# EMMC_SD.net
KiCad netlist of a schematic drawn in Altium Designer
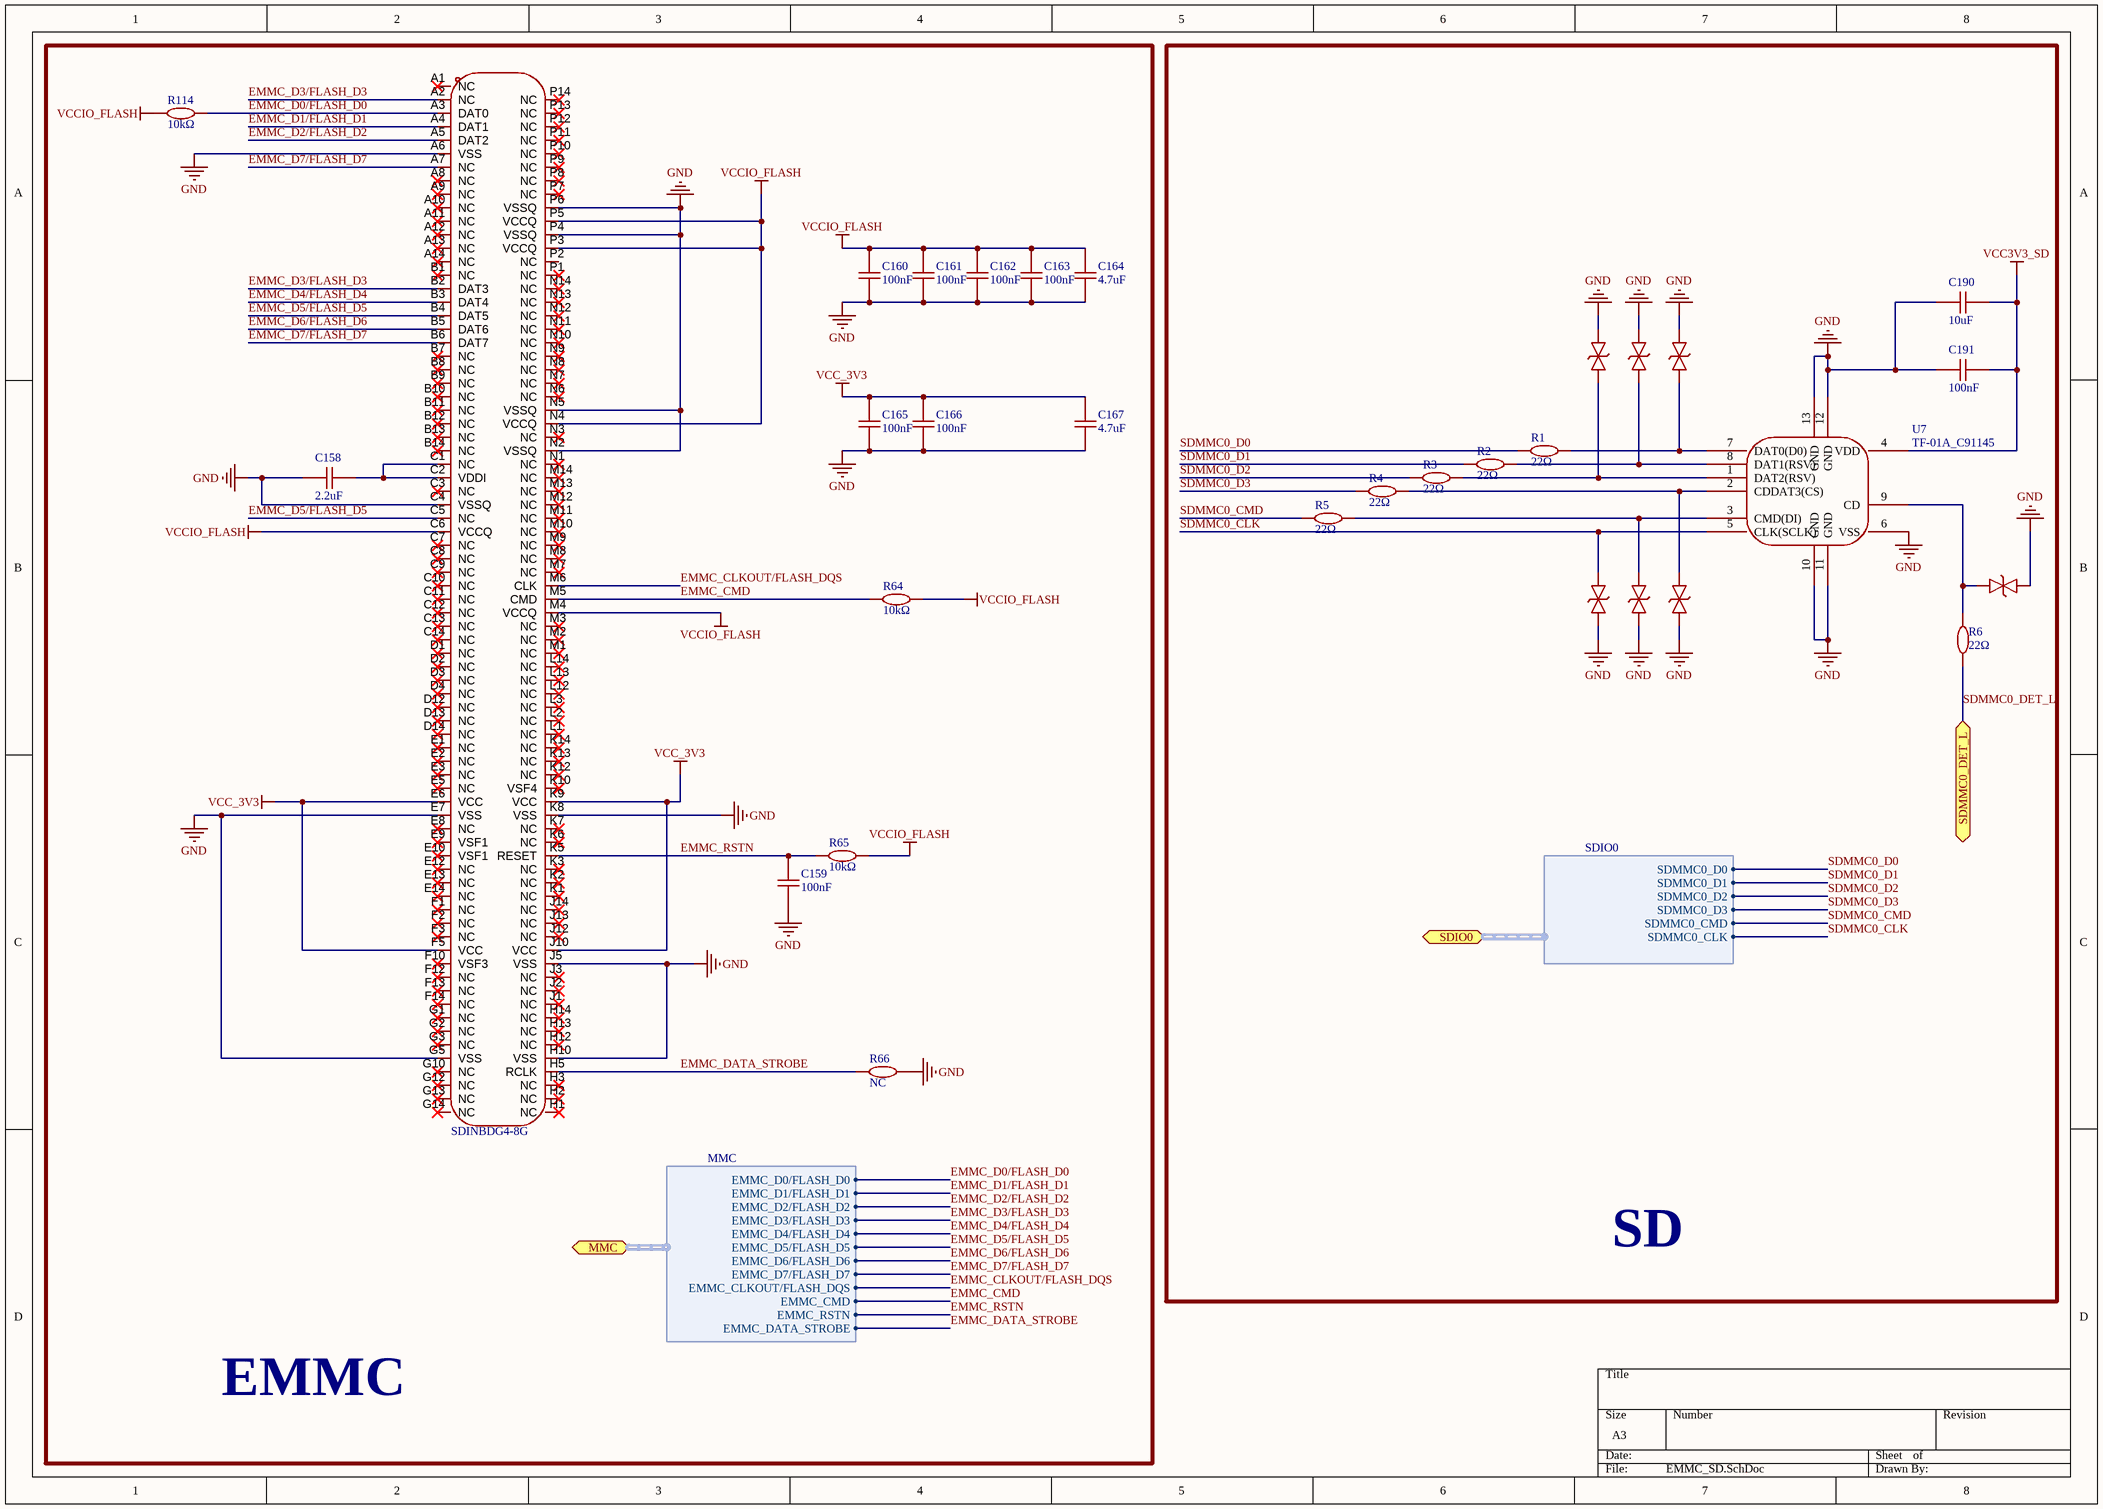
[diagram p0: EMMC_SD.SchDoc]

(export (version "E")
  (design (tool "Eeschema 10.0.6"))
  (components
    (comp (ref "C158")
      (value "2.2uF")
      (footprint "C0402")
      (description "50V 2.2uF NP0 0402 Ceramic Capacitors ROHS")
      (libsource (lib "RLC") (part "2.2uF"))
    )
    (comp (ref "C159")
      (value "100nF")
      (footprint "C0402")
      (description "50V 100nF X7R ±10% 0402 Ceramic Capacitors ROHS")
      (libsource (lib "RLC") (part "100nF"))
    )
    (comp (ref "C160")
      (value "100nF")
      (footprint "C0402")
      (description "50V 100nF X7R ±10% 0402 Ceramic Capacitors ROHS")
      (libsource (lib "RLC") (part "100nF"))
    )
    (comp (ref "C161")
      (value "100nF")
      (footprint "C0402")
      (description "50V 100nF X7R ±10% 0402 Ceramic Capacitors ROHS")
      (libsource (lib "RLC") (part "100nF"))
    )
    (comp (ref "C162")
      (value "100nF")
      (footprint "C0402")
      (description "50V 100nF X7R ±10% 0402 Ceramic Capacitors ROHS")
      (libsource (lib "RLC") (part "100nF"))
    )
    (comp (ref "C163")
      (value "100nF")
      (footprint "C0402")
      (description "50V 100nF X7R ±10% 0402 Ceramic Capacitors ROHS")
      (libsource (lib "RLC") (part "100nF"))
    )
    (comp (ref "C164")
      (value "4.7uF")
      (footprint "C0402")
      (description "10V 4.7uF X5R ±20% 0402 Ceramic Capacitors ROHS")
      (libsource (lib "RLC") (part "4.7uF"))
    )
    (comp (ref "C165")
      (value "100nF")
      (footprint "C0402")
      (description "50V 100nF X7R ±10% 0402 Ceramic Capacitors ROHS")
      (libsource (lib "RLC") (part "100nF"))
    )
    (comp (ref "C166")
      (value "100nF")
      (footprint "C0402")
      (description "50V 100nF X7R ±10% 0402 Ceramic Capacitors ROHS")
      (libsource (lib "RLC") (part "100nF"))
    )
    (comp (ref "C167")
      (value "4.7uF")
      (footprint "C0402")
      (description "10V 4.7uF X5R ±20% 0402 Ceramic Capacitors ROHS")
      (libsource (lib "RLC") (part "4.7uF"))
    )
    (comp (ref "C190")
      (value "10uF")
      (footprint "C0603")
      (description "10V 10uF X5R ±10% 0603 Ceramic Capacitors ROHS")
      (libsource (lib "RLC") (part "10uF"))
    )
    (comp (ref "C191")
      (value "100nF")
      (footprint "C0402")
      (description "50V 100nF X7R ±10% 0402 Ceramic Capacitors ROHS")
      (libsource (lib "RLC") (part "100nF"))
    )
    (comp (ref "R1")
      (value "22Ω")
      (footprint "R0402")
      (description "62.5mW 33Ω 50V ±100ppm/℃ Thick Film Resistor ±1% 0402 Chip Resistor - Surface Mount ROHS")
      (libsource (lib "RLC") (part "22Ω"))
    )
    (comp (ref "R2")
      (value "22Ω")
      (footprint "R0402")
      (description "62.5mW 33Ω 50V ±100ppm/℃ Thick Film Resistor ±1% 0402 Chip Resistor - Surface Mount ROHS")
      (libsource (lib "RLC") (part "22Ω"))
    )
    (comp (ref "R3")
      (value "22Ω")
      (footprint "R0402")
      (description "62.5mW 33Ω 50V ±100ppm/℃ Thick Film Resistor ±1% 0402 Chip Resistor - Surface Mount ROHS")
      (libsource (lib "RLC") (part "22Ω"))
    )
    (comp (ref "R4")
      (value "22Ω")
      (footprint "R0402")
      (description "62.5mW 33Ω 50V ±100ppm/℃ Thick Film Resistor ±1% 0402 Chip Resistor - Surface Mount ROHS")
      (libsource (lib "RLC") (part "22Ω"))
    )
    (comp (ref "R5")
      (value "22Ω")
      (footprint "R0402")
      (description "62.5mW 33Ω 50V ±100ppm/℃ Thick Film Resistor ±1% 0402 Chip Resistor - Surface Mount ROHS")
      (libsource (lib "RLC") (part "22Ω"))
    )
    (comp (ref "R6")
      (value "22Ω")
      (footprint "R0402")
      (description "62.5mW 33Ω 50V ±100ppm/℃ Thick Film Resistor ±1% 0402 Chip Resistor - Surface Mount ROHS")
      (libsource (lib "RLC") (part "22Ω"))
    )
    (comp (ref "R64")
      (value "10kΩ")
      (footprint "R0402")
      (description "62.5mW 10kΩ 50V ±100ppm/℃ Thick Film Resistor ±1% 0402 Chip Resistor - Surface Mount ROHS")
      (libsource (lib "RLC") (part "10kΩ"))
    )
    (comp (ref "R65")
      (value "10kΩ")
      (footprint "R0402")
      (description "62.5mW 10kΩ 50V ±100ppm/℃ Thick Film Resistor ±1% 0402 Chip Resistor - Surface Mount ROHS")
      (libsource (lib "RLC") (part "10kΩ"))
    )
    (comp (ref "R66")
      (value "NC")
      (footprint "R0402")
      (description "62.5mW 10kΩ 50V ±100ppm/℃ Thick Film Resistor ±1% 0402 Chip Resistor - Surface Mount ROHS")
      (libsource (lib "RLC") (part "10kΩ"))
    )
    (comp (ref "R114")
      (value "10kΩ")
      (footprint "R0402")
      (description "62.5mW 10kΩ 50V ±100ppm/℃ Thick Film Resistor ±1% 0402 Chip Resistor - Surface Mount ROHS")
      (libsource (lib "RLC") (part "10kΩ"))
    )
    (comp (ref "U3")
      (value "SDINBDG4-8G")
      (footprint "FBGA-153_L13.0-W11.5-P0.50_KLMAG1JETD-B041")
      (libsource (lib "IC") (part "SDINBDG4-8G"))
    )
    (comp (ref "U4")
      (value "ESD5451N")
      (footprint "DFN1006-2L-BI")
      (description "9A 9.8V 8V Bidirectional 5V DFN1006-2L TVS Diodes ROHS")
      (fields (field (name "MANUFACTURER") "HXY MOSFET(华轩阳电子)"))
      (libsource (lib "LED") (part "ESD5451N_C5261080"))
    )
    (comp (ref "U5")
      (value "ESD5451N")
      (footprint "DFN1006-2L-BI")
      (description "9A 9.8V 8V Bidirectional 5V DFN1006-2L TVS Diodes ROHS")
      (fields (field (name "MANUFACTURER") "HXY MOSFET(华轩阳电子)"))
      (libsource (lib "LED") (part "ESD5451N_C5261080"))
    )
    (comp (ref "U6")
      (value "ESD5451N")
      (footprint "DFN1006-2L-BI")
      (description "9A 9.8V 8V Bidirectional 5V DFN1006-2L TVS Diodes ROHS")
      (fields (field (name "MANUFACTURER") "HXY MOSFET(华轩阳电子)"))
      (libsource (lib "LED") (part "ESD5451N_C5261080"))
    )
    (comp (ref "U7")
      (value "TF-01A_C91145")
      (footprint "TF-SMD_TF-01A")
      (description "Push-Push 1.85mm Connector and Ejector MicroSD Card (TF Card) SMD PC Card Sockets ROHS")
      (libsource (lib "IC") (part "TF-01A_C91145"))
    )
    (comp (ref "U8")
      (value "ESD5451N")
      (footprint "DFN1006-2L-BI")
      (description "9A 9.8V 8V Bidirectional 5V DFN1006-2L TVS Diodes ROHS")
      (fields (field (name "MANUFACTURER") "HXY MOSFET(华轩阳电子)"))
      (libsource (lib "LED") (part "ESD5451N_C5261080"))
    )
    (comp (ref "U9")
      (value "ESD5451N")
      (footprint "DFN1006-2L-BI")
      (description "9A 9.8V 8V Bidirectional 5V DFN1006-2L TVS Diodes ROHS")
      (fields (field (name "MANUFACTURER") "HXY MOSFET(华轩阳电子)"))
      (libsource (lib "LED") (part "ESD5451N_C5261080"))
    )
    (comp (ref "U10")
      (value "ESD5451N")
      (footprint "DFN1006-2L-BI")
      (description "9A 9.8V 8V Bidirectional 5V DFN1006-2L TVS Diodes ROHS")
      (fields (field (name "MANUFACTURER") "HXY MOSFET(华轩阳电子)"))
      (libsource (lib "LED") (part "ESD5451N_C5261080"))
    )
    (comp (ref "U11")
      (value "ESD5451N")
      (footprint "DFN1006-2L-BI")
      (description "9A 9.8V 8V Bidirectional 5V DFN1006-2L TVS Diodes ROHS")
      (fields (field (name "MANUFACTURER") "HXY MOSFET(华轩阳电子)"))
      (libsource (lib "LED") (part "ESD5451N_C5261080"))
    )
  )
  (nets
    (net (code "3") (name "/EMMC_CLKOUT{slash}FLASH_DQS") (class "Default")
      (node (ref "U3") (pin "M6") (pinfunction "CLK_M6") (pintype "passive"))
    )
    (net (code "4") (name "/EMMC_CMD") (class "Default")
      (node (ref "R64") (pin "1") (pinfunction "1_1") (pintype "passive"))
      (node (ref "U3") (pin "M5") (pinfunction "CMD_M5") (pintype "passive"))
    )
    (net (code "5") (name "/EMMC_D0{slash}FLASH_D0") (class "Default")
      (node (ref "R114") (pin "2") (pinfunction "2_2") (pintype "passive"))
      (node (ref "U3") (pin "A3") (pinfunction "DAT0_A3") (pintype "passive"))
    )
    (net (code "6") (name "/EMMC_D1{slash}FLASH_D1") (class "Default")
      (node (ref "U3") (pin "A4") (pinfunction "DAT1_A4") (pintype "passive"))
    )
    (net (code "7") (name "/EMMC_D2{slash}FLASH_D2") (class "Default")
      (node (ref "U3") (pin "A5") (pinfunction "DAT2_A5") (pintype "passive"))
    )
    (net (code "8") (name "/EMMC_D3{slash}FLASH_D3") (class "Default")
      (node (ref "U3") (pin "A2") (pinfunction "NC_A2") (pintype "passive"))
      (node (ref "U3") (pin "B2") (pinfunction "DAT3_B2") (pintype "passive"))
    )
    (net (code "9") (name "/EMMC_D4{slash}FLASH_D4") (class "Default")
      (node (ref "U3") (pin "B3") (pinfunction "DAT4_B3") (pintype "passive"))
    )
    (net (code "10") (name "/EMMC_D5{slash}FLASH_D5") (class "Default")
      (node (ref "U3") (pin "B4") (pinfunction "DAT5_B4") (pintype "passive"))
      (node (ref "U3") (pin "C5") (pinfunction "NC_C5") (pintype "passive"))
    )
    (net (code "11") (name "/EMMC_D6{slash}FLASH_D6") (class "Default")
      (node (ref "U3") (pin "B5") (pinfunction "DAT6_B5") (pintype "passive"))
    )
    (net (code "12") (name "/EMMC_D7{slash}FLASH_D7") (class "Default")
      (node (ref "U3") (pin "A7") (pinfunction "NC_A7") (pintype "passive"))
      (node (ref "U3") (pin "B6") (pinfunction "DAT7_B6") (pintype "passive"))
    )
    (net (code "13") (name "/EMMC_DATA_STROBE") (class "Default")
      (node (ref "R66") (pin "1") (pinfunction "1_1") (pintype "passive"))
      (node (ref "U3") (pin "H5") (pinfunction "RCLK_H5") (pintype "passive"))
    )
    (net (code "14") (name "/EMMC_RSTN") (class "Default")
      (node (ref "C159") (pin "2") (pinfunction "2_2") (pintype "passive"))
      (node (ref "R65") (pin "1") (pinfunction "1_1") (pintype "passive"))
      (node (ref "U3") (pin "K5") (pinfunction "RESET_K5") (pintype "passive"))
    )
    (net (code "15") (name "/SDMMC0_CLK") (class "Default")
      (node (ref "U7") (pin "5") (pinfunction "CLK(SCLK)_5") (pintype "passive"))
      (node (ref "U8") (pin "2") (pinfunction "2_2") (pintype "passive"))
    )
    (net (code "16") (name "/SDMMC0_CMD") (class "Default")
      (node (ref "R5") (pin "1") (pinfunction "1_1") (pintype "passive"))
    )
    (net (code "17") (name "/SDMMC0_D0") (class "Default")
      (node (ref "R1") (pin "1") (pinfunction "1_1") (pintype "passive"))
    )
    (net (code "18") (name "/SDMMC0_D1") (class "Default")
      (node (ref "R2") (pin "1") (pinfunction "1_1") (pintype "passive"))
    )
    (net (code "19") (name "/SDMMC0_D2") (class "Default")
      (node (ref "R3") (pin "1") (pinfunction "1_1") (pintype "passive"))
    )
    (net (code "20") (name "/SDMMC0_D3") (class "Default")
      (node (ref "R4") (pin "1") (pinfunction "1_1") (pintype "passive"))
    )
    (net (code "21") (name "/SDMMC0_DET_L") (class "Default")
      (node (ref "R6") (pin "1") (pinfunction "1_1") (pintype "passive"))
    )
    (net (code "24") (name "GND") (class "Default")
      (node (ref "C158") (pin "1") (pinfunction "1_1") (pintype "passive"))
      (node (ref "C159") (pin "1") (pinfunction "1_1") (pintype "passive"))
      (node (ref "C160") (pin "1") (pinfunction "1_1") (pintype "passive"))
      (node (ref "C161") (pin "1") (pinfunction "1_1") (pintype "passive"))
      (node (ref "C162") (pin "1") (pinfunction "1_1") (pintype "passive"))
      (node (ref "C163") (pin "1") (pinfunction "1_1") (pintype "passive"))
      (node (ref "C164") (pin "1") (pinfunction "1_1") (pintype "passive"))
      (node (ref "C165") (pin "1") (pinfunction "1_1") (pintype "passive"))
      (node (ref "C166") (pin "1") (pinfunction "1_1") (pintype "passive"))
      (node (ref "C167") (pin "1") (pinfunction "1_1") (pintype "passive"))
      (node (ref "C190") (pin "1") (pinfunction "1_1") (pintype "passive"))
      (node (ref "C191") (pin "1") (pinfunction "1_1") (pintype "passive"))
      (node (ref "R66") (pin "2") (pinfunction "2_2") (pintype "passive"))
      (node (ref "U10") (pin "1") (pinfunction "1_1") (pintype "passive"))
      (node (ref "U11") (pin "1") (pinfunction "1_1") (pintype "passive"))
      (node (ref "U3") (pin "A6") (pinfunction "VSS_A6") (pintype "passive"))
      (node (ref "U3") (pin "C4") (pinfunction "VSSQ_C4") (pintype "passive"))
      (node (ref "U3") (pin "E7") (pinfunction "VSS_E7") (pintype "passive"))
      (node (ref "U3") (pin "G5") (pinfunction "VSS_G5") (pintype "passive"))
      (node (ref "U3") (pin "H10") (pinfunction "VSS_H10") (pintype "passive"))
      (node (ref "U3") (pin "J5") (pinfunction "VSS_J5") (pintype "passive"))
      (node (ref "U3") (pin "K8") (pinfunction "VSS_K8") (pintype "passive"))
      (node (ref "U3") (pin "N2") (pinfunction "VSSQ_N2") (pintype "passive"))
      (node (ref "U3") (pin "N5") (pinfunction "VSSQ_N5") (pintype "passive"))
      (node (ref "U3") (pin "P4") (pinfunction "VSSQ_P4") (pintype "passive"))
      (node (ref "U3") (pin "P6") (pinfunction "VSSQ_P6") (pintype "passive"))
      (node (ref "U4") (pin "2") (pinfunction "2_2") (pintype "passive"))
      (node (ref "U5") (pin "2") (pinfunction "2_2") (pintype "passive"))
      (node (ref "U6") (pin "2") (pinfunction "2_2") (pintype "passive"))
      (node (ref "U7") (pin "10") (pinfunction "GND_10") (pintype "passive"))
      (node (ref "U7") (pin "11") (pinfunction "GND_11") (pintype "passive"))
      (node (ref "U7") (pin "12") (pinfunction "GND_12") (pintype "passive"))
      (node (ref "U7") (pin "13") (pinfunction "GND_13") (pintype "passive"))
      (node (ref "U7") (pin "6") (pinfunction "VSS_6") (pintype "passive"))
      (node (ref "U8") (pin "1") (pinfunction "1_1") (pintype "passive"))
      (node (ref "U9") (pin "1") (pinfunction "1_1") (pintype "passive"))
    )
    (net (code "25") (name "Net-(U3-VDDI)") (class "Default")
      (node (ref "C158") (pin "2") (pinfunction "2_2") (pintype "passive"))
      (node (ref "U3") (pin "C1") (pinfunction "NC_C1") (pintype "passive"))
      (node (ref "U3") (pin "C2") (pinfunction "VDDI_C2") (pintype "passive"))
    )
    (net (code "26") (name "Net-(U7-CD)") (class "Default")
      (node (ref "R6") (pin "2") (pinfunction "2_2") (pintype "passive"))
      (node (ref "U11") (pin "2") (pinfunction "2_2") (pintype "passive"))
      (node (ref "U7") (pin "9") (pinfunction "CD_9") (pintype "passive"))
    )
    (net (code "27") (name "Net-(U7-CDDAT3(CS))") (class "Default")
      (node (ref "R4") (pin "2") (pinfunction "2_2") (pintype "passive"))
      (node (ref "U10") (pin "2") (pinfunction "2_2") (pintype "passive"))
      (node (ref "U7") (pin "2") (pinfunction "CDDAT3(CS)_2") (pintype "passive"))
    )
    (net (code "28") (name "Net-(U7-CMD(DI))") (class "Default")
      (node (ref "R5") (pin "2") (pinfunction "2_2") (pintype "passive"))
      (node (ref "U7") (pin "3") (pinfunction "CMD(DI)_3") (pintype "passive"))
      (node (ref "U9") (pin "2") (pinfunction "2_2") (pintype "passive"))
    )
    (net (code "29") (name "Net-(U7-DAT0(D0))") (class "Default")
      (node (ref "R1") (pin "2") (pinfunction "2_2") (pintype "passive"))
      (node (ref "U6") (pin "1") (pinfunction "1_1") (pintype "passive"))
      (node (ref "U7") (pin "7") (pinfunction "DAT0(D0)_7") (pintype "passive"))
    )
    (net (code "30") (name "Net-(U7-DAT1(RSV))") (class "Default")
      (node (ref "R2") (pin "2") (pinfunction "2_2") (pintype "passive"))
      (node (ref "U5") (pin "1") (pinfunction "1_1") (pintype "passive"))
      (node (ref "U7") (pin "8") (pinfunction "DAT1(RSV)_8") (pintype "passive"))
    )
    (net (code "31") (name "Net-(U7-DAT2(RSV))") (class "Default")
      (node (ref "R3") (pin "2") (pinfunction "2_2") (pintype "passive"))
      (node (ref "U4") (pin "1") (pinfunction "1_1") (pintype "passive"))
      (node (ref "U7") (pin "1") (pinfunction "DAT2(RSV)_1") (pintype "passive"))
    )
    (net (code "32") (name "VCC3V3_SD") (class "Default")
      (node (ref "C190") (pin "2") (pinfunction "2_2") (pintype "passive"))
      (node (ref "C191") (pin "2") (pinfunction "2_2") (pintype "passive"))
      (node (ref "U7") (pin "4") (pinfunction "VDD_4") (pintype "passive"))
    )
    (net (code "33") (name "VCCIO_FLASH") (class "Default")
      (node (ref "C160") (pin "2") (pinfunction "2_2") (pintype "passive"))
      (node (ref "C161") (pin "2") (pinfunction "2_2") (pintype "passive"))
      (node (ref "C162") (pin "2") (pinfunction "2_2") (pintype "passive"))
      (node (ref "C163") (pin "2") (pinfunction "2_2") (pintype "passive"))
      (node (ref "C164") (pin "2") (pinfunction "2_2") (pintype "passive"))
      (node (ref "R114") (pin "1") (pinfunction "1_1") (pintype "passive"))
      (node (ref "R64") (pin "2") (pinfunction "2_2") (pintype "passive"))
      (node (ref "R65") (pin "2") (pinfunction "2_2") (pintype "passive"))
      (node (ref "U3") (pin "C6") (pinfunction "VCCQ_C6") (pintype "passive"))
      (node (ref "U3") (pin "M4") (pinfunction "VCCQ_M4") (pintype "passive"))
      (node (ref "U3") (pin "N4") (pinfunction "VCCQ_N4") (pintype "passive"))
      (node (ref "U3") (pin "P3") (pinfunction "VCCQ_P3") (pintype "passive"))
      (node (ref "U3") (pin "P5") (pinfunction "VCCQ_P5") (pintype "passive"))
    )
    (net (code "34") (name "VCC_3V3") (class "Default")
      (node (ref "C165") (pin "2") (pinfunction "2_2") (pintype "passive"))
      (node (ref "C166") (pin "2") (pinfunction "2_2") (pintype "passive"))
      (node (ref "C167") (pin "2") (pinfunction "2_2") (pintype "passive"))
      (node (ref "U3") (pin "E6") (pinfunction "VCC_E6") (pintype "passive"))
      (node (ref "U3") (pin "F5") (pinfunction "VCC_F5") (pintype "passive"))
      (node (ref "U3") (pin "J10") (pinfunction "VCC_J10") (pintype "passive"))
      (node (ref "U3") (pin "K9") (pinfunction "VCC_K9") (pintype "passive"))
    )
    (net (code "35") (name "unconnected-(U3-NC-PadA1)") (class "Default")
      (node (ref "U3") (pin "A1") (pinfunction "NC_A1") (pintype "passive+no_connect"))
    )
    (net (code "36") (name "unconnected-(U3-NC-PadA8)") (class "Default")
      (node (ref "U3") (pin "A8") (pinfunction "NC_A8") (pintype "passive+no_connect"))
    )
    (net (code "37") (name "unconnected-(U3-NC-PadA9)") (class "Default")
      (node (ref "U3") (pin "A9") (pinfunction "NC_A9") (pintype "passive+no_connect"))
    )
    (net (code "38") (name "unconnected-(U3-NC-PadA10)") (class "Default")
      (node (ref "U3") (pin "A10") (pinfunction "NC_A10") (pintype "passive+no_connect"))
    )
    (net (code "39") (name "unconnected-(U3-NC-PadA11)") (class "Default")
      (node (ref "U3") (pin "A11") (pinfunction "NC_A11") (pintype "passive+no_connect"))
    )
    (net (code "40") (name "unconnected-(U3-NC-PadA12)") (class "Default")
      (node (ref "U3") (pin "A12") (pinfunction "NC_A12") (pintype "passive+no_connect"))
    )
    (net (code "41") (name "unconnected-(U3-NC-PadA13)") (class "Default")
      (node (ref "U3") (pin "A13") (pinfunction "NC_A13") (pintype "passive+no_connect"))
    )
    (net (code "42") (name "unconnected-(U3-NC-PadA14)") (class "Default")
      (node (ref "U3") (pin "A14") (pinfunction "NC_A14") (pintype "passive+no_connect"))
    )
    (net (code "43") (name "unconnected-(U3-NC-PadB1)") (class "Default")
      (node (ref "U3") (pin "B1") (pinfunction "NC_B1") (pintype "passive+no_connect"))
    )
    (net (code "44") (name "unconnected-(U3-NC-PadB7)") (class "Default")
      (node (ref "U3") (pin "B7") (pinfunction "NC_B7") (pintype "passive+no_connect"))
    )
    (net (code "45") (name "unconnected-(U3-NC-PadB8)") (class "Default")
      (node (ref "U3") (pin "B8") (pinfunction "NC_B8") (pintype "passive+no_connect"))
    )
    (net (code "46") (name "unconnected-(U3-NC-PadB9)") (class "Default")
      (node (ref "U3") (pin "B9") (pinfunction "NC_B9") (pintype "passive+no_connect"))
    )
    (net (code "47") (name "unconnected-(U3-NC-PadB10)") (class "Default")
      (node (ref "U3") (pin "B10") (pinfunction "NC_B10") (pintype "passive+no_connect"))
    )
    (net (code "48") (name "unconnected-(U3-NC-PadB11)") (class "Default")
      (node (ref "U3") (pin "B11") (pinfunction "NC_B11") (pintype "passive+no_connect"))
    )
    (net (code "49") (name "unconnected-(U3-NC-PadB12)") (class "Default")
      (node (ref "U3") (pin "B12") (pinfunction "NC_B12") (pintype "passive+no_connect"))
    )
    (net (code "50") (name "unconnected-(U3-NC-PadB13)") (class "Default")
      (node (ref "U3") (pin "B13") (pinfunction "NC_B13") (pintype "passive+no_connect"))
    )
    (net (code "51") (name "unconnected-(U3-NC-PadB14)") (class "Default")
      (node (ref "U3") (pin "B14") (pinfunction "NC_B14") (pintype "passive+no_connect"))
    )
    (net (code "52") (name "unconnected-(U3-NC-PadC3)") (class "Default")
      (node (ref "U3") (pin "C3") (pinfunction "NC_C3") (pintype "passive+no_connect"))
    )
    (net (code "53") (name "unconnected-(U3-NC-PadC7)") (class "Default")
      (node (ref "U3") (pin "C7") (pinfunction "NC_C7") (pintype "passive+no_connect"))
    )
    (net (code "54") (name "unconnected-(U3-NC-PadC8)") (class "Default")
      (node (ref "U3") (pin "C8") (pinfunction "NC_C8") (pintype "passive+no_connect"))
    )
    (net (code "55") (name "unconnected-(U3-NC-PadC9)") (class "Default")
      (node (ref "U3") (pin "C9") (pinfunction "NC_C9") (pintype "passive+no_connect"))
    )
    (net (code "56") (name "unconnected-(U3-NC-PadC10)") (class "Default")
      (node (ref "U3") (pin "C10") (pinfunction "NC_C10") (pintype "passive+no_connect"))
    )
    (net (code "57") (name "unconnected-(U3-NC-PadC11)") (class "Default")
      (node (ref "U3") (pin "C11") (pinfunction "NC_C11") (pintype "passive+no_connect"))
    )
    (net (code "58") (name "unconnected-(U3-NC-PadC12)") (class "Default")
      (node (ref "U3") (pin "C12") (pinfunction "NC_C12") (pintype "passive+no_connect"))
    )
    (net (code "59") (name "unconnected-(U3-NC-PadC13)") (class "Default")
      (node (ref "U3") (pin "C13") (pinfunction "NC_C13") (pintype "passive+no_connect"))
    )
    (net (code "60") (name "unconnected-(U3-NC-PadC14)") (class "Default")
      (node (ref "U3") (pin "C14") (pinfunction "NC_C14") (pintype "passive+no_connect"))
    )
    (net (code "61") (name "unconnected-(U3-NC-PadD1)") (class "Default")
      (node (ref "U3") (pin "D1") (pinfunction "NC_D1") (pintype "passive+no_connect"))
    )
    (net (code "62") (name "unconnected-(U3-NC-PadD2)") (class "Default")
      (node (ref "U3") (pin "D2") (pinfunction "NC_D2") (pintype "passive+no_connect"))
    )
    (net (code "63") (name "unconnected-(U3-NC-PadD3)") (class "Default")
      (node (ref "U3") (pin "D3") (pinfunction "NC_D3") (pintype "passive+no_connect"))
    )
    (net (code "64") (name "unconnected-(U3-NC-PadD4)") (class "Default")
      (node (ref "U3") (pin "D4") (pinfunction "NC_D4") (pintype "passive+no_connect"))
    )
    (net (code "65") (name "unconnected-(U3-NC-PadD12)") (class "Default")
      (node (ref "U3") (pin "D12") (pinfunction "NC_D12") (pintype "passive+no_connect"))
    )
    (net (code "66") (name "unconnected-(U3-NC-PadD13)") (class "Default")
      (node (ref "U3") (pin "D13") (pinfunction "NC_D13") (pintype "passive+no_connect"))
    )
    (net (code "67") (name "unconnected-(U3-NC-PadD14)") (class "Default")
      (node (ref "U3") (pin "D14") (pinfunction "NC_D14") (pintype "passive+no_connect"))
    )
    (net (code "68") (name "unconnected-(U3-NC-PadE1)") (class "Default")
      (node (ref "U3") (pin "E1") (pinfunction "NC_E1") (pintype "passive+no_connect"))
    )
    (net (code "69") (name "unconnected-(U3-NC-PadE2)") (class "Default")
      (node (ref "U3") (pin "E2") (pinfunction "NC_E2") (pintype "passive+no_connect"))
    )
    (net (code "70") (name "unconnected-(U3-NC-PadE3)") (class "Default")
      (node (ref "U3") (pin "E3") (pinfunction "NC_E3") (pintype "passive+no_connect"))
    )
    (net (code "71") (name "unconnected-(U3-NC-PadE5)") (class "Default")
      (node (ref "U3") (pin "E5") (pinfunction "NC_E5") (pintype "passive+no_connect"))
    )
    (net (code "72") (name "unconnected-(U3-NC-PadE8)") (class "Default")
      (node (ref "U3") (pin "E8") (pinfunction "NC_E8") (pintype "passive+no_connect"))
    )
    (net (code "73") (name "unconnected-(U3-NC-PadE12)") (class "Default")
      (node (ref "U3") (pin "E12") (pinfunction "NC_E12") (pintype "passive+no_connect"))
    )
    (net (code "74") (name "unconnected-(U3-NC-PadE13)") (class "Default")
      (node (ref "U3") (pin "E13") (pinfunction "NC_E13") (pintype "passive+no_connect"))
    )
    (net (code "75") (name "unconnected-(U3-NC-PadE14)") (class "Default")
      (node (ref "U3") (pin "E14") (pinfunction "NC_E14") (pintype "passive+no_connect"))
    )
    (net (code "76") (name "unconnected-(U3-NC-PadF1)") (class "Default")
      (node (ref "U3") (pin "F1") (pinfunction "NC_F1") (pintype "passive+no_connect"))
    )
    (net (code "77") (name "unconnected-(U3-NC-PadF2)") (class "Default")
      (node (ref "U3") (pin "F2") (pinfunction "NC_F2") (pintype "passive+no_connect"))
    )
    (net (code "78") (name "unconnected-(U3-NC-PadF3)") (class "Default")
      (node (ref "U3") (pin "F3") (pinfunction "NC_F3") (pintype "passive+no_connect"))
    )
    (net (code "79") (name "unconnected-(U3-NC-PadF12)") (class "Default")
      (node (ref "U3") (pin "F12") (pinfunction "NC_F12") (pintype "passive+no_connect"))
    )
    (net (code "80") (name "unconnected-(U3-NC-PadF13)") (class "Default")
      (node (ref "U3") (pin "F13") (pinfunction "NC_F13") (pintype "passive+no_connect"))
    )
    (net (code "81") (name "unconnected-(U3-NC-PadF14)") (class "Default")
      (node (ref "U3") (pin "F14") (pinfunction "NC_F14") (pintype "passive+no_connect"))
    )
    (net (code "82") (name "unconnected-(U3-NC-PadG1)") (class "Default")
      (node (ref "U3") (pin "G1") (pinfunction "NC_G1") (pintype "passive+no_connect"))
    )
    (net (code "83") (name "unconnected-(U3-NC-PadG2)") (class "Default")
      (node (ref "U3") (pin "G2") (pinfunction "NC_G2") (pintype "passive+no_connect"))
    )
    (net (code "84") (name "unconnected-(U3-NC-PadG3)") (class "Default")
      (node (ref "U3") (pin "G3") (pinfunction "NC_G3") (pintype "passive+no_connect"))
    )
    (net (code "85") (name "unconnected-(U3-NC-PadG10)") (class "Default")
      (node (ref "U3") (pin "G10") (pinfunction "NC_G10") (pintype "passive+no_connect"))
    )
    (net (code "86") (name "unconnected-(U3-NC-PadG12)") (class "Default")
      (node (ref "U3") (pin "G12") (pinfunction "NC_G12") (pintype "passive+no_connect"))
    )
    (net (code "87") (name "unconnected-(U3-NC-PadG13)") (class "Default")
      (node (ref "U3") (pin "G13") (pinfunction "NC_G13") (pintype "passive+no_connect"))
    )
    (net (code "88") (name "unconnected-(U3-NC-PadG14)") (class "Default")
      (node (ref "U3") (pin "G14") (pinfunction "NC_G14") (pintype "passive+no_connect"))
    )
    (net (code "89") (name "unconnected-(U3-NC-PadH1)") (class "Default")
      (node (ref "U3") (pin "H1") (pinfunction "NC_H1") (pintype "passive+no_connect"))
    )
    (net (code "90") (name "unconnected-(U3-NC-PadH2)") (class "Default")
      (node (ref "U3") (pin "H2") (pinfunction "NC_H2") (pintype "passive+no_connect"))
    )
    (net (code "91") (name "unconnected-(U3-NC-PadH3)") (class "Default")
      (node (ref "U3") (pin "H3") (pinfunction "NC_H3") (pintype "passive+no_connect"))
    )
    (net (code "92") (name "unconnected-(U3-NC-PadH12)") (class "Default")
      (node (ref "U3") (pin "H12") (pinfunction "NC_H12") (pintype "passive+no_connect"))
    )
    (net (code "93") (name "unconnected-(U3-NC-PadH13)") (class "Default")
      (node (ref "U3") (pin "H13") (pinfunction "NC_H13") (pintype "passive+no_connect"))
    )
    (net (code "94") (name "unconnected-(U3-NC-PadH14)") (class "Default")
      (node (ref "U3") (pin "H14") (pinfunction "NC_H14") (pintype "passive+no_connect"))
    )
    (net (code "95") (name "unconnected-(U3-NC-PadJ1)") (class "Default")
      (node (ref "U3") (pin "J1") (pinfunction "NC_J1") (pintype "passive+no_connect"))
    )
    (net (code "96") (name "unconnected-(U3-NC-PadJ2)") (class "Default")
      (node (ref "U3") (pin "J2") (pinfunction "NC_J2") (pintype "passive+no_connect"))
    )
    (net (code "97") (name "unconnected-(U3-NC-PadJ3)") (class "Default")
      (node (ref "U3") (pin "J3") (pinfunction "NC_J3") (pintype "passive+no_connect"))
    )
    (net (code "98") (name "unconnected-(U3-NC-PadJ12)") (class "Default")
      (node (ref "U3") (pin "J12") (pinfunction "NC_J12") (pintype "passive+no_connect"))
    )
    (net (code "99") (name "unconnected-(U3-NC-PadJ13)") (class "Default")
      (node (ref "U3") (pin "J13") (pinfunction "NC_J13") (pintype "passive+no_connect"))
    )
    (net (code "100") (name "unconnected-(U3-NC-PadJ14)") (class "Default")
      (node (ref "U3") (pin "J14") (pinfunction "NC_J14") (pintype "passive+no_connect"))
    )
    (net (code "101") (name "unconnected-(U3-NC-PadK1)") (class "Default")
      (node (ref "U3") (pin "K1") (pinfunction "NC_K1") (pintype "passive+no_connect"))
    )
    (net (code "102") (name "unconnected-(U3-NC-PadK2)") (class "Default")
      (node (ref "U3") (pin "K2") (pinfunction "NC_K2") (pintype "passive+no_connect"))
    )
    (net (code "103") (name "unconnected-(U3-NC-PadK3)") (class "Default")
      (node (ref "U3") (pin "K3") (pinfunction "NC_K3") (pintype "passive+no_connect"))
    )
    (net (code "104") (name "unconnected-(U3-NC-PadK6)") (class "Default")
      (node (ref "U3") (pin "K6") (pinfunction "NC_K6") (pintype "passive+no_connect"))
    )
    (net (code "105") (name "unconnected-(U3-NC-PadK7)") (class "Default")
      (node (ref "U3") (pin "K7") (pinfunction "NC_K7") (pintype "passive+no_connect"))
    )
    (net (code "106") (name "unconnected-(U3-NC-PadK12)") (class "Default")
      (node (ref "U3") (pin "K12") (pinfunction "NC_K12") (pintype "passive+no_connect"))
    )
    (net (code "107") (name "unconnected-(U3-NC-PadK13)") (class "Default")
      (node (ref "U3") (pin "K13") (pinfunction "NC_K13") (pintype "passive+no_connect"))
    )
    (net (code "108") (name "unconnected-(U3-NC-PadK14)") (class "Default")
      (node (ref "U3") (pin "K14") (pinfunction "NC_K14") (pintype "passive+no_connect"))
    )
    (net (code "109") (name "unconnected-(U3-NC-PadL1)") (class "Default")
      (node (ref "U3") (pin "L1") (pinfunction "NC_L1") (pintype "passive+no_connect"))
    )
    (net (code "110") (name "unconnected-(U3-NC-PadL2)") (class "Default")
      (node (ref "U3") (pin "L2") (pinfunction "NC_L2") (pintype "passive+no_connect"))
    )
    (net (code "111") (name "unconnected-(U3-NC-PadL3)") (class "Default")
      (node (ref "U3") (pin "L3") (pinfunction "NC_L3") (pintype "passive+no_connect"))
    )
    (net (code "112") (name "unconnected-(U3-NC-PadL12)") (class "Default")
      (node (ref "U3") (pin "L12") (pinfunction "NC_L12") (pintype "passive+no_connect"))
    )
    (net (code "113") (name "unconnected-(U3-NC-PadL13)") (class "Default")
      (node (ref "U3") (pin "L13") (pinfunction "NC_L13") (pintype "passive+no_connect"))
    )
    (net (code "114") (name "unconnected-(U3-NC-PadL14)") (class "Default")
      (node (ref "U3") (pin "L14") (pinfunction "NC_L14") (pintype "passive+no_connect"))
    )
    (net (code "115") (name "unconnected-(U3-NC-PadM1)") (class "Default")
      (node (ref "U3") (pin "M1") (pinfunction "NC_M1") (pintype "passive+no_connect"))
    )
    (net (code "116") (name "unconnected-(U3-NC-PadM2)") (class "Default")
      (node (ref "U3") (pin "M2") (pinfunction "NC_M2") (pintype "passive+no_connect"))
    )
    (net (code "117") (name "unconnected-(U3-NC-PadM3)") (class "Default")
      (node (ref "U3") (pin "M3") (pinfunction "NC_M3") (pintype "passive+no_connect"))
    )
    (net (code "118") (name "unconnected-(U3-NC-PadM7)") (class "Default")
      (node (ref "U3") (pin "M7") (pinfunction "NC_M7") (pintype "passive+no_connect"))
    )
    (net (code "119") (name "unconnected-(U3-NC-PadM8)") (class "Default")
      (node (ref "U3") (pin "M8") (pinfunction "NC_M8") (pintype "passive+no_connect"))
    )
    (net (code "120") (name "unconnected-(U3-NC-PadM9)") (class "Default")
      (node (ref "U3") (pin "M9") (pinfunction "NC_M9") (pintype "passive+no_connect"))
    )
    (net (code "121") (name "unconnected-(U3-NC-PadM10)") (class "Default")
      (node (ref "U3") (pin "M10") (pinfunction "NC_M10") (pintype "passive+no_connect"))
    )
    (net (code "122") (name "unconnected-(U3-NC-PadM11)") (class "Default")
      (node (ref "U3") (pin "M11") (pinfunction "NC_M11") (pintype "passive+no_connect"))
    )
    (net (code "123") (name "unconnected-(U3-NC-PadM12)") (class "Default")
      (node (ref "U3") (pin "M12") (pinfunction "NC_M12") (pintype "passive+no_connect"))
    )
    (net (code "124") (name "unconnected-(U3-NC-PadM13)") (class "Default")
      (node (ref "U3") (pin "M13") (pinfunction "NC_M13") (pintype "passive+no_connect"))
    )
    (net (code "125") (name "unconnected-(U3-NC-PadM14)") (class "Default")
      (node (ref "U3") (pin "M14") (pinfunction "NC_M14") (pintype "passive+no_connect"))
    )
    (net (code "126") (name "unconnected-(U3-NC-PadN1)") (class "Default")
      (node (ref "U3") (pin "N1") (pinfunction "NC_N1") (pintype "passive+no_connect"))
    )
    (net (code "127") (name "unconnected-(U3-NC-PadN3)") (class "Default")
      (node (ref "U3") (pin "N3") (pinfunction "NC_N3") (pintype "passive+no_connect"))
    )
    (net (code "128") (name "unconnected-(U3-NC-PadN6)") (class "Default")
      (node (ref "U3") (pin "N6") (pinfunction "NC_N6") (pintype "passive+no_connect"))
    )
    (net (code "129") (name "unconnected-(U3-NC-PadN7)") (class "Default")
      (node (ref "U3") (pin "N7") (pinfunction "NC_N7") (pintype "passive+no_connect"))
    )
    (net (code "130") (name "unconnected-(U3-NC-PadN8)") (class "Default")
      (node (ref "U3") (pin "N8") (pinfunction "NC_N8") (pintype "passive+no_connect"))
    )
    (net (code "131") (name "unconnected-(U3-NC-PadN9)") (class "Default")
      (node (ref "U3") (pin "N9") (pinfunction "NC_N9") (pintype "passive+no_connect"))
    )
    (net (code "132") (name "unconnected-(U3-NC-PadN10)") (class "Default")
      (node (ref "U3") (pin "N10") (pinfunction "NC_N10") (pintype "passive+no_connect"))
    )
    (net (code "133") (name "unconnected-(U3-NC-PadN11)") (class "Default")
      (node (ref "U3") (pin "N11") (pinfunction "NC_N11") (pintype "passive+no_connect"))
    )
    (net (code "134") (name "unconnected-(U3-NC-PadN12)") (class "Default")
      (node (ref "U3") (pin "N12") (pinfunction "NC_N12") (pintype "passive+no_connect"))
    )
    (net (code "135") (name "unconnected-(U3-NC-PadN13)") (class "Default")
      (node (ref "U3") (pin "N13") (pinfunction "NC_N13") (pintype "passive+no_connect"))
    )
    (net (code "136") (name "unconnected-(U3-NC-PadN14)") (class "Default")
      (node (ref "U3") (pin "N14") (pinfunction "NC_N14") (pintype "passive+no_connect"))
    )
    (net (code "137") (name "unconnected-(U3-NC-PadP1)") (class "Default")
      (node (ref "U3") (pin "P1") (pinfunction "NC_P1") (pintype "passive+no_connect"))
    )
    (net (code "138") (name "unconnected-(U3-NC-PadP2)") (class "Default")
      (node (ref "U3") (pin "P2") (pinfunction "NC_P2") (pintype "passive"))
    )
    (net (code "139") (name "unconnected-(U3-NC-PadP7)") (class "Default")
      (node (ref "U3") (pin "P7") (pinfunction "NC_P7") (pintype "passive+no_connect"))
    )
    (net (code "140") (name "unconnected-(U3-NC-PadP8)") (class "Default")
      (node (ref "U3") (pin "P8") (pinfunction "NC_P8") (pintype "passive+no_connect"))
    )
    (net (code "141") (name "unconnected-(U3-NC-PadP9)") (class "Default")
      (node (ref "U3") (pin "P9") (pinfunction "NC_P9") (pintype "passive+no_connect"))
    )
    (net (code "142") (name "unconnected-(U3-NC-PadP10)") (class "Default")
      (node (ref "U3") (pin "P10") (pinfunction "NC_P10") (pintype "passive+no_connect"))
    )
    (net (code "143") (name "unconnected-(U3-NC-PadP11)") (class "Default")
      (node (ref "U3") (pin "P11") (pinfunction "NC_P11") (pintype "passive+no_connect"))
    )
    (net (code "144") (name "unconnected-(U3-NC-PadP12)") (class "Default")
      (node (ref "U3") (pin "P12") (pinfunction "NC_P12") (pintype "passive+no_connect"))
    )
    (net (code "145") (name "unconnected-(U3-NC-PadP13)") (class "Default")
      (node (ref "U3") (pin "P13") (pinfunction "NC_P13") (pintype "passive+no_connect"))
    )
    (net (code "146") (name "unconnected-(U3-NC-PadP14)") (class "Default")
      (node (ref "U3") (pin "P14") (pinfunction "NC_P14") (pintype "passive+no_connect"))
    )
    (net (code "147") (name "unconnected-(U3-VSF1-PadE9)") (class "Default")
      (node (ref "U3") (pin "E9") (pinfunction "VSF1_E9") (pintype "passive+no_connect"))
    )
    (net (code "148") (name "unconnected-(U3-VSF1-PadE10)") (class "Default")
      (node (ref "U3") (pin "E10") (pinfunction "VSF1_E10") (pintype "passive+no_connect"))
    )
    (net (code "149") (name "unconnected-(U3-VSF3-PadF10)") (class "Default")
      (node (ref "U3") (pin "F10") (pinfunction "VSF3_F10") (pintype "passive+no_connect"))
    )
    (net (code "150") (name "unconnected-(U3-VSF4-PadK10)") (class "Default")
      (node (ref "U3") (pin "K10") (pinfunction "VSF4_K10") (pintype "passive+no_connect"))
    )
  )
)
